# Sheet1.net
KiCad netlist of a schematic drawn in Altium Designer
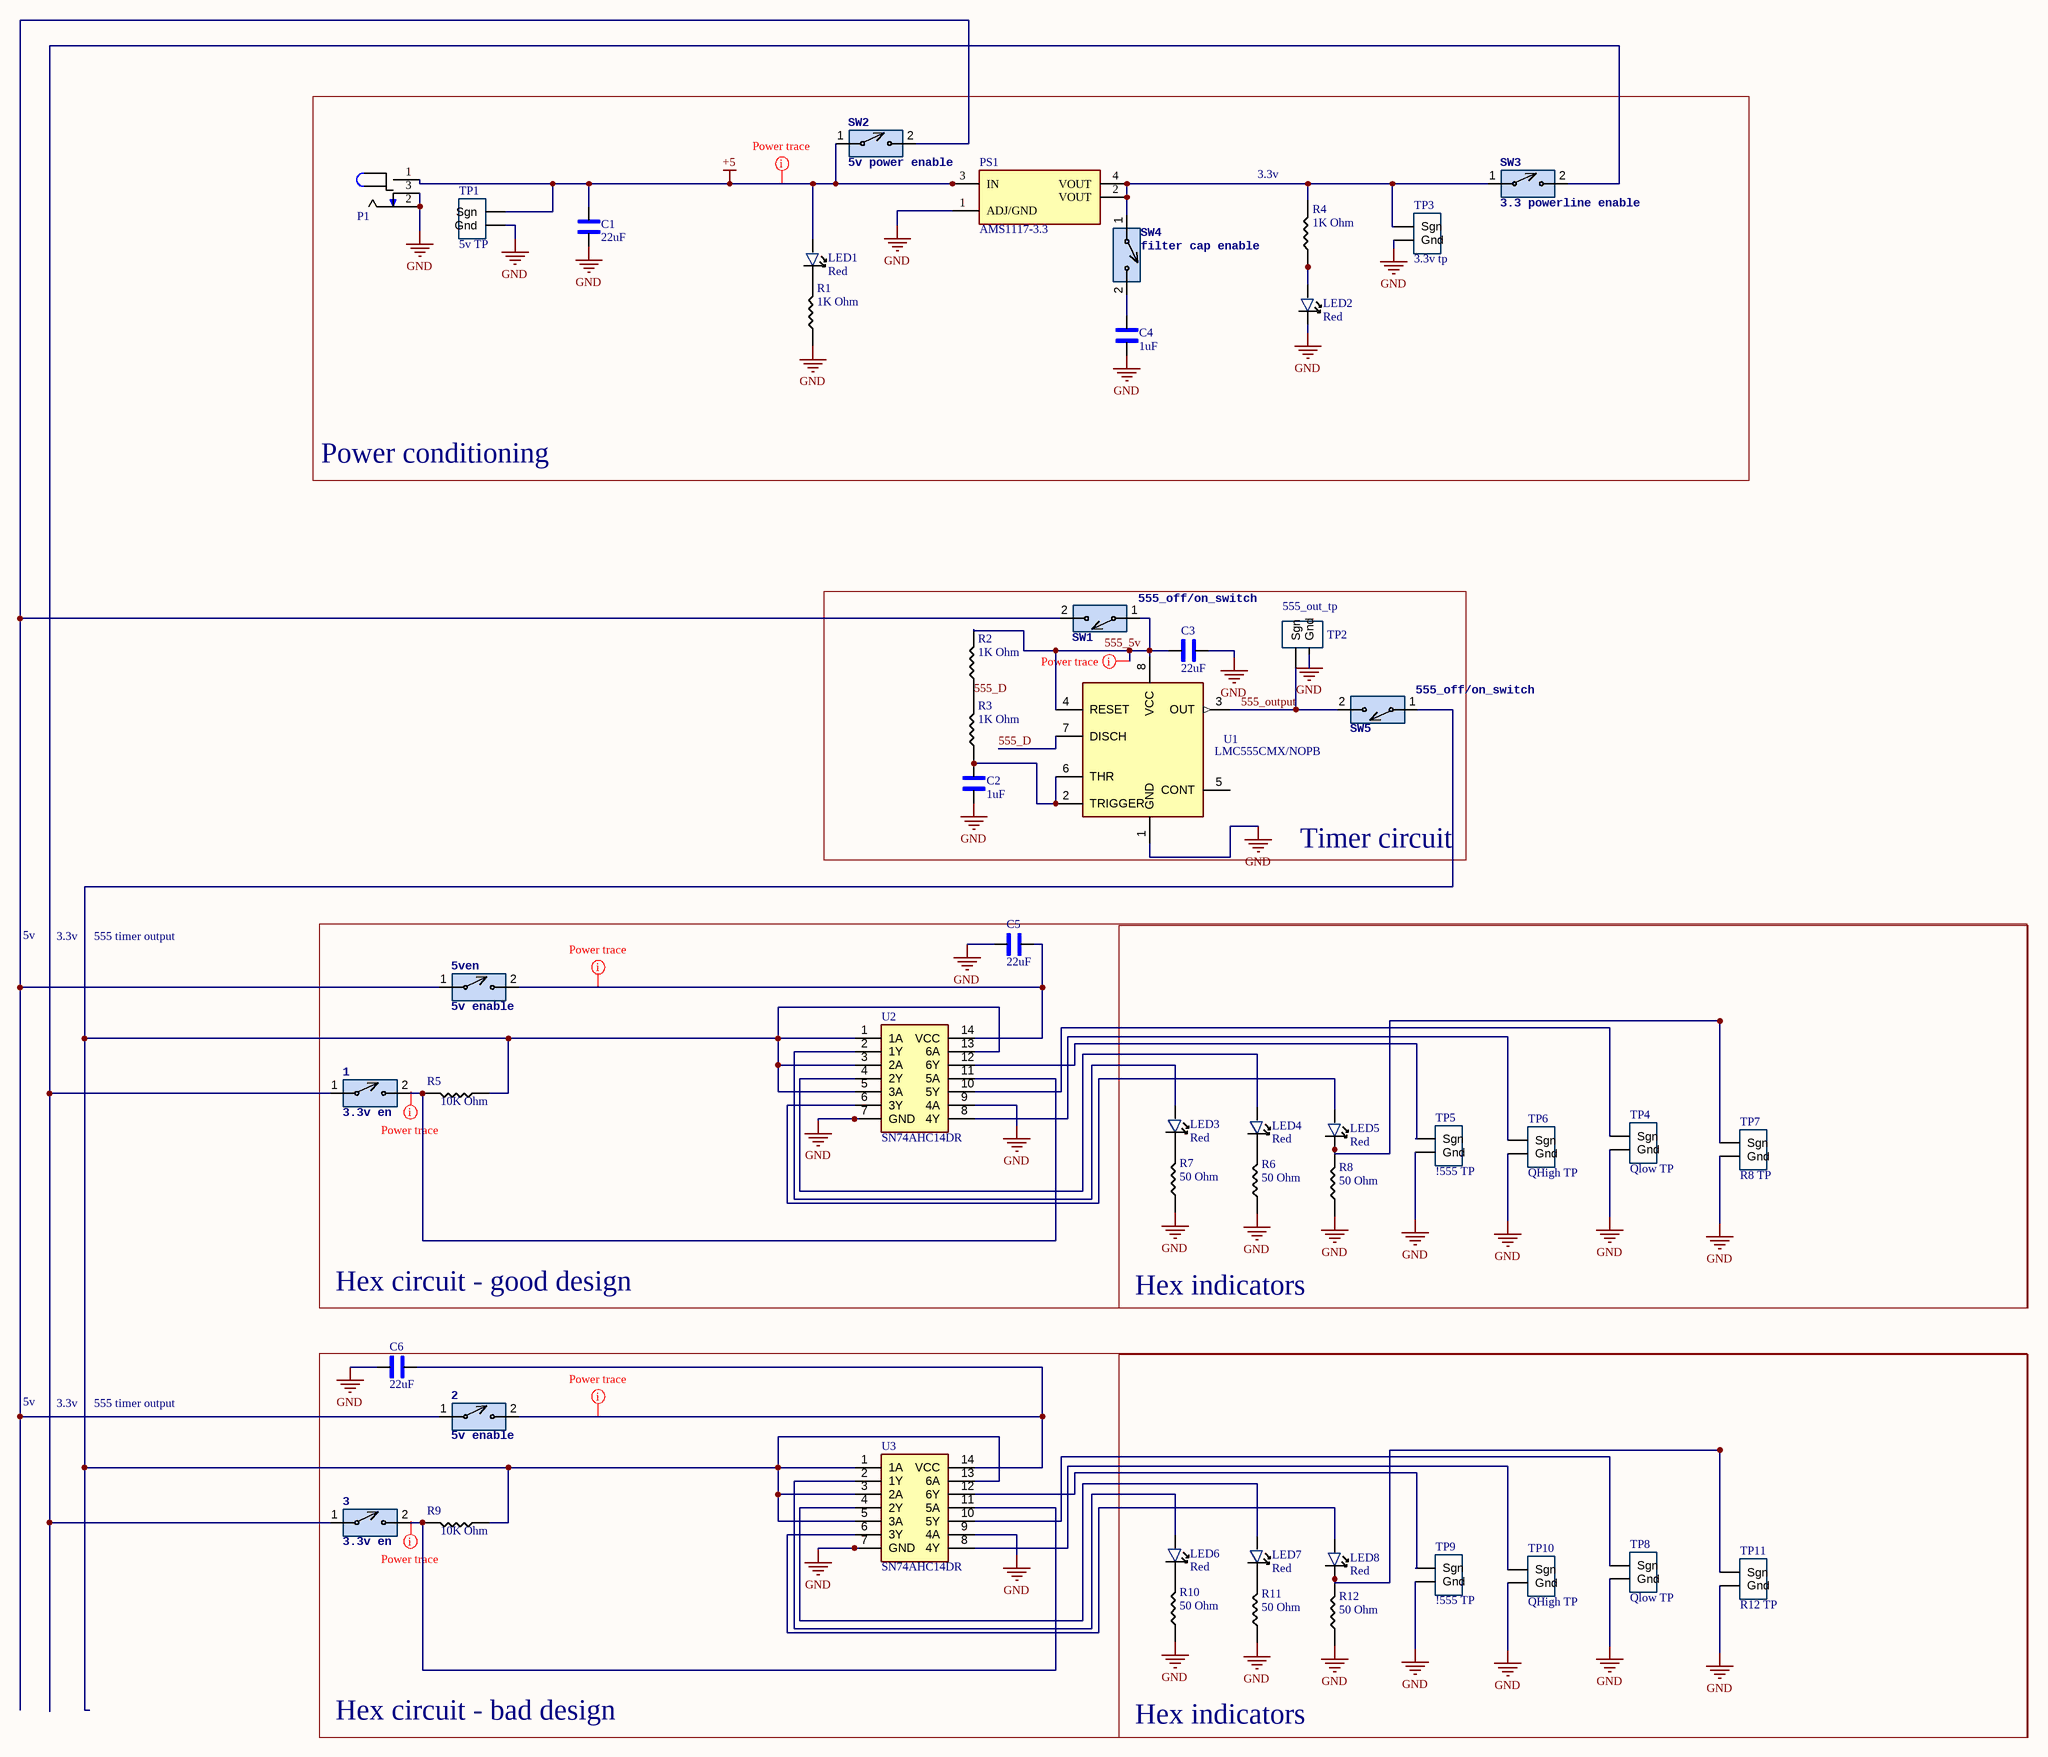
[diagram p0: Sheet1.SchDoc]

(export (version "E")
  (design (tool "Eeschema 10.0.6"))
  (components
    (comp (ref "1")
      (value "3.3v en")
      (footprint "2Pin-Header-Conn")
      (description "2Pin Header")
      (fields (field (name "LCSC PART#") "C124375"))
      (libsource (lib "ECEN5730Lib_2023_05_DS") (part "SW_2Pin_100mil_Switch"))
    )
    (comp (ref "2")
      (value "5v enable")
      (footprint "2Pin-Header-Conn")
      (description "2Pin Header")
      (fields (field (name "LCSC PART#") "C124375"))
      (libsource (lib "ECEN5730Lib_2023_05_DS") (part "SW_2Pin_100mil_Switch"))
    )
    (comp (ref "3")
      (value "3.3v en")
      (footprint "2Pin-Header-Conn")
      (description "2Pin Header")
      (fields (field (name "LCSC PART#") "C124375"))
      (libsource (lib "ECEN5730Lib_2023_05_DS") (part "SW_2Pin_100mil_Switch"))
    )
    (comp (ref "5ven")
      (value "5v enable")
      (footprint "2Pin-Header-Conn")
      (description "2Pin Header")
      (fields (field (name "LCSC PART#") "C124375"))
      (libsource (lib "ECEN5730Lib_2023_05_DS") (part "SW_2Pin_100mil_Switch"))
    )
    (comp (ref "C1")
      (value "22uF")
      (footprint "1206_Passive_Capacitor")
      (description "22uF ±10% 25V X5R 1206 Multilayer Ceramic Capacitors MLCC - SMD/SMT RoHS")
      (fields (field (name "MFR PART #") "CL31A226KAHNNNE") (field (name "LCSC PART#") "C12891"))
      (libsource (lib "ECEN5730Lib_2023_05_DS") (part "C_22uF_1206"))
    )
    (comp (ref "C2")
      (value "1uF")
      (footprint "1206_Passive_Capacitor")
      (description "MULTILAYER CERAMIC CAPACITORS MLCC - SMD/SMT 1UF 50V 1206 ROHS")
      (fields (field (name "MFR PART #") "CL31B105KBHNNNE") (field (name "LCSC PART#") "C1848"))
      (libsource (lib "ECEN5730Lib_2023_05_DS") (part "C_1uF_1206"))
    )
    (comp (ref "C3")
      (value "22uF")
      (footprint "1206_Passive_Capacitor")
      (description "22uF ±10% 25V X5R 1206 Multilayer Ceramic Capacitors MLCC - SMD/SMT RoHS")
      (fields (field (name "MFR PART #") "CL31A226KAHNNNE") (field (name "LCSC PART#") "C12891"))
      (libsource (lib "ECEN5730Lib_2023_05_DS") (part "C_22uF_1206"))
    )
    (comp (ref "C4")
      (value "1uF")
      (footprint "1206_Passive_Capacitor")
      (description "MULTILAYER CERAMIC CAPACITORS MLCC - SMD/SMT 1UF 50V 1206 ROHS")
      (fields (field (name "MFR PART #") "CL31B105KBHNNNE") (field (name "LCSC PART#") "C1848"))
      (libsource (lib "ECEN5730Lib_2023_05_DS") (part "C_1uF_1206"))
    )
    (comp (ref "C5")
      (value "22uF")
      (footprint "1206_Passive_Capacitor")
      (description "22uF ±10% 25V X5R 1206 Multilayer Ceramic Capacitors MLCC - SMD/SMT RoHS")
      (fields (field (name "MFR PART #") "CL31A226KAHNNNE") (field (name "LCSC PART#") "C12891"))
      (libsource (lib "ECEN5730Lib_2023_05_DS") (part "C_22uF_1206"))
    )
    (comp (ref "C6")
      (value "22uF")
      (footprint "1206_Passive_Capacitor")
      (description "22uF ±10% 25V X5R 1206 Multilayer Ceramic Capacitors MLCC - SMD/SMT RoHS")
      (fields (field (name "MFR PART #") "CL31A226KAHNNNE") (field (name "LCSC PART#") "C12891"))
      (libsource (lib "ECEN5730Lib_2023_05_DS") (part "C_22uF_1206"))
    )
    (comp (ref "LED1")
      (value "Red")
      (footprint "LED_1206")
      (description "Red 621~631nm 1206 Light Emitting Diodes (LED) RoHS")
      (fields (field (name "MFR PART #") "15-21/R6C-FQ1R1B/2T") (field (name "LCSC PART#") "C93133"))
      (libsource (lib "ECEN5730Lib_2023_05_DS") (part "LED_RED_1206"))
    )
    (comp (ref "LED2")
      (value "Red")
      (footprint "LED_1206")
      (description "Red 621~631nm 1206 Light Emitting Diodes (LED) RoHS")
      (fields (field (name "MFR PART #") "15-21/R6C-FQ1R1B/2T") (field (name "LCSC PART#") "C93133"))
      (libsource (lib "ECEN5730Lib_2023_05_DS") (part "LED_RED_1206"))
    )
    (comp (ref "LED3")
      (value "Red")
      (footprint "LED_1206")
      (description "Red 621~631nm 1206 Light Emitting Diodes (LED) RoHS")
      (fields (field (name "MFR PART #") "15-21/R6C-FQ1R1B/2T") (field (name "LCSC PART#") "C93133"))
      (libsource (lib "ECEN5730Lib_2023_05_DS") (part "LED_RED_1206"))
    )
    (comp (ref "LED4")
      (value "Red")
      (footprint "LED_1206")
      (description "Red 621~631nm 1206 Light Emitting Diodes (LED) RoHS")
      (fields (field (name "MFR PART #") "15-21/R6C-FQ1R1B/2T") (field (name "LCSC PART#") "C93133"))
      (libsource (lib "ECEN5730Lib_2023_05_DS") (part "LED_RED_1206"))
    )
    (comp (ref "LED5")
      (value "Red")
      (footprint "LED_1206")
      (description "Red 621~631nm 1206 Light Emitting Diodes (LED) RoHS")
      (fields (field (name "MFR PART #") "15-21/R6C-FQ1R1B/2T") (field (name "LCSC PART#") "C93133"))
      (libsource (lib "ECEN5730Lib_2023_05_DS") (part "LED_RED_1206"))
    )
    (comp (ref "LED6")
      (value "Red")
      (footprint "LED_1206")
      (description "Red 621~631nm 1206 Light Emitting Diodes (LED) RoHS")
      (fields (field (name "MFR PART #") "15-21/R6C-FQ1R1B/2T") (field (name "LCSC PART#") "C93133"))
      (libsource (lib "ECEN5730Lib_2023_05_DS") (part "LED_RED_1206"))
    )
    (comp (ref "LED7")
      (value "Red")
      (footprint "LED_1206")
      (description "Red 621~631nm 1206 Light Emitting Diodes (LED) RoHS")
      (fields (field (name "MFR PART #") "15-21/R6C-FQ1R1B/2T") (field (name "LCSC PART#") "C93133"))
      (libsource (lib "ECEN5730Lib_2023_05_DS") (part "LED_RED_1206"))
    )
    (comp (ref "LED8")
      (value "Red")
      (footprint "LED_1206")
      (description "Red 621~631nm 1206 Light Emitting Diodes (LED) RoHS")
      (fields (field (name "MFR PART #") "15-21/R6C-FQ1R1B/2T") (field (name "LCSC PART#") "C93133"))
      (libsource (lib "ECEN5730Lib_2023_05_DS") (part "LED_RED_1206"))
    )
    (comp (ref "P1")
      (value "Power Jack")
      (footprint "Power_Jack")
      (description "Power Barrel Connector Jack 2.10mm ID (0.083\"), 5.50mm OD (0.217\") Through Hole, Right Angle")
      (fields (field (name "MFR PART #") "PJ-102A") (field (name "LCSC PART#") "C136744"))
      (libsource (lib "ECEN5730Lib_2023_05_DS") (part "P_Power Jack"))
    )
    (comp (ref "PS1")
      (value "AMS1117-3.3")
      (footprint "LDO")
      (description "LOW DROPOUT REGULATORS(LDO) POSITIVE FIXED 1.3V @ 800MA 15V 3.3V 1A SOT-223 ROHS")
      (fields (field (name "LCSC PART#") "C6186"))
      (libsource (lib "ECEN5730Lib_2023_05_DS") (part "PS_AMS_LDO_3v3"))
    )
    (comp (ref "R1")
      (value "1K Ohm")
      (footprint "1206_Passive_Resitor")
      (description "CHIP RESISTOR - SURFACE MOUNT 1KOHMS ±1% 1/4W 1206 ROHS")
      (fields (field (name "MFR PART #") "RNCP1206FTD1K00CT") (field (name "LCSC PART#") "C4410"))
      (libsource (lib "ECEN5730Lib_2023_05_DS") (part "R_1K_1206"))
    )
    (comp (ref "R2")
      (value "1K Ohm")
      (footprint "1206_Passive_Resitor")
      (description "CHIP RESISTOR - SURFACE MOUNT 1KOHMS ±1% 1/4W 1206 ROHS")
      (fields (field (name "MFR PART #") "RNCP1206FTD1K00CT") (field (name "LCSC PART#") "C4410"))
      (libsource (lib "ECEN5730Lib_2023_05_DS") (part "R_1K_1206"))
    )
    (comp (ref "R3")
      (value "1K Ohm")
      (footprint "1206_Passive_Resitor")
      (description "CHIP RESISTOR - SURFACE MOUNT 1KOHMS ±1% 1/4W 1206 ROHS")
      (fields (field (name "MFR PART #") "RNCP1206FTD1K00CT") (field (name "LCSC PART#") "C4410"))
      (libsource (lib "ECEN5730Lib_2023_05_DS") (part "R_1K_1206"))
    )
    (comp (ref "R4")
      (value "1K Ohm")
      (footprint "1206_Passive_Resitor")
      (description "CHIP RESISTOR - SURFACE MOUNT 1KOHMS ±1% 1/4W 1206 ROHS")
      (fields (field (name "MFR PART #") "RNCP1206FTD1K00CT") (field (name "LCSC PART#") "C4410"))
      (libsource (lib "ECEN5730Lib_2023_05_DS") (part "R_1K_1206"))
    )
    (comp (ref "R5")
      (value "10K Ohm")
      (footprint "1206_Passive_Resitor")
      (description "CHIP RESISTOR - SURFACE MOUNT 1KOHMS ±1% 1/4W 1206 ROHS")
      (fields (field (name "MFR PART #") "RNCP1206FTD1K00CT") (field (name "LCSC PART#") "C4410"))
      (libsource (lib "ECEN5730Lib_2023_05_DS") (part "R_1K_1206"))
    )
    (comp (ref "R6")
      (value "50 Ohm")
      (footprint "1206_Passive_Resitor")
      (description "CHIP RESISTOR - SURFACE MOUNT 100MOHMS ±1% 1/4W 1206 ROHS")
      (fields (field (name "MFR PART #") "1206W4F1006T5E") (field (name "LCSC PART#") "C59781"))
      (libsource (lib "ECEN5730Lib_2023_05_DS") (part "R_100M_1206_1"))
    )
    (comp (ref "R7")
      (value "50 Ohm")
      (footprint "1206_Passive_Resitor")
      (description "CHIP RESISTOR - SURFACE MOUNT 100MOHMS ±1% 1/4W 1206 ROHS")
      (fields (field (name "MFR PART #") "1206W4F1006T5E") (field (name "LCSC PART#") "C59781"))
      (libsource (lib "ECEN5730Lib_2023_05_DS") (part "R_100M_1206_1"))
    )
    (comp (ref "R8")
      (value "50 Ohm")
      (footprint "1206_Passive_Resitor")
      (description "CHIP RESISTOR - SURFACE MOUNT 100MOHMS ±1% 1/4W 1206 ROHS")
      (fields (field (name "MFR PART #") "1206W4F1006T5E") (field (name "LCSC PART#") "C59781"))
      (libsource (lib "ECEN5730Lib_2023_05_DS") (part "R_100M_1206_1"))
    )
    (comp (ref "R9")
      (value "10K Ohm")
      (footprint "1206_Passive_Resitor")
      (description "CHIP RESISTOR - SURFACE MOUNT 1KOHMS ±1% 1/4W 1206 ROHS")
      (fields (field (name "MFR PART #") "RNCP1206FTD1K00CT") (field (name "LCSC PART#") "C4410"))
      (libsource (lib "ECEN5730Lib_2023_05_DS") (part "R_1K_1206"))
    )
    (comp (ref "R10")
      (value "50 Ohm")
      (footprint "1206_Passive_Resitor")
      (description "CHIP RESISTOR - SURFACE MOUNT 100MOHMS ±1% 1/4W 1206 ROHS")
      (fields (field (name "MFR PART #") "1206W4F1006T5E") (field (name "LCSC PART#") "C59781"))
      (libsource (lib "ECEN5730Lib_2023_05_DS") (part "R_100M_1206_1"))
    )
    (comp (ref "R11")
      (value "50 Ohm")
      (footprint "1206_Passive_Resitor")
      (description "CHIP RESISTOR - SURFACE MOUNT 100MOHMS ±1% 1/4W 1206 ROHS")
      (fields (field (name "MFR PART #") "1206W4F1006T5E") (field (name "LCSC PART#") "C59781"))
      (libsource (lib "ECEN5730Lib_2023_05_DS") (part "R_100M_1206_1"))
    )
    (comp (ref "R12")
      (value "50 Ohm")
      (footprint "1206_Passive_Resitor")
      (description "CHIP RESISTOR - SURFACE MOUNT 100MOHMS ±1% 1/4W 1206 ROHS")
      (fields (field (name "MFR PART #") "1206W4F1006T5E") (field (name "LCSC PART#") "C59781"))
      (libsource (lib "ECEN5730Lib_2023_05_DS") (part "R_100M_1206_1"))
    )
    (comp (ref "SW1")
      (value "555_off/on_switch")
      (footprint "2Pin-Header-Conn")
      (description "2Pin Header")
      (fields (field (name "LCSC PART#") "C124375"))
      (libsource (lib "") (part "SW_2Pin_100mil_Switch_1"))
    )
    (comp (ref "SW2")
      (value "5v power enable")
      (footprint "2Pin-Header-Conn")
      (description "2Pin Header")
      (fields (field (name "LCSC PART#") "C124375"))
      (libsource (lib "ECEN5730Lib_2023_05_DS") (part "SW_2Pin_100mil_Switch"))
    )
    (comp (ref "SW3")
      (value "3.3 powerline enable")
      (footprint "2Pin-Header-Conn")
      (description "2Pin Header")
      (fields (field (name "LCSC PART#") "C124375"))
      (libsource (lib "ECEN5730Lib_2023_05_DS") (part "SW_2Pin_100mil_Switch"))
    )
    (comp (ref "SW4")
      (value "filter cap enable")
      (footprint "2Pin-Header-Conn")
      (description "2Pin Header")
      (fields (field (name "LCSC PART#") "C124375"))
      (libsource (lib "") (part "SW_2Pin_100mil_Switch_2"))
    )
    (comp (ref "SW5")
      (value "555_off/on_switch")
      (footprint "2Pin-Header-Conn")
      (description "2Pin Header")
      (fields (field (name "LCSC PART#") "C124375"))
      (libsource (lib "") (part "SW_2Pin_100mil_Switch_1"))
    )
    (comp (ref "TP1")
      (value "5v TP")
      (footprint "TP10x_Probe")
      (description "Test Point 300 mil centers")
      (libsource (lib "") (part "TP_10x_Probe_1"))
    )
    (comp (ref "TP2")
      (value "555_out_tp")
      (footprint "TP10x_Probe")
      (description "Test Point 300 mil centers")
      (libsource (lib "") (part "TP_10x_Probe_2"))
    )
    (comp (ref "TP3")
      (value "3.3v tp")
      (footprint "TP10x_Probe")
      (description "Test Point 300 mil centers")
      (libsource (lib "ECEN5730Lib_2023_05_DS") (part "TP_10x_Probe"))
    )
    (comp (ref "TP4")
      (value "Qlow TP")
      (footprint "TP10x_Probe")
      (description "Test Point 300 mil centers")
      (libsource (lib "ECEN5730Lib_2023_05_DS") (part "TP_10x_Probe"))
    )
    (comp (ref "TP5")
      (value "!555 TP")
      (footprint "TP10x_Probe")
      (description "Test Point 300 mil centers")
      (libsource (lib "ECEN5730Lib_2023_05_DS") (part "TP_10x_Probe"))
    )
    (comp (ref "TP6")
      (value "QHigh TP")
      (footprint "TP10x_Probe")
      (description "Test Point 300 mil centers")
      (libsource (lib "ECEN5730Lib_2023_05_DS") (part "TP_10x_Probe"))
    )
    (comp (ref "TP7")
      (value "R8 TP")
      (footprint "TP10x_Probe")
      (description "Test Point 300 mil centers")
      (libsource (lib "ECEN5730Lib_2023_05_DS") (part "TP_10x_Probe"))
    )
    (comp (ref "TP8")
      (value "Qlow TP")
      (footprint "TP10x_Probe")
      (description "Test Point 300 mil centers")
      (libsource (lib "ECEN5730Lib_2023_05_DS") (part "TP_10x_Probe"))
    )
    (comp (ref "TP9")
      (value "!555 TP")
      (footprint "TP10x_Probe")
      (description "Test Point 300 mil centers")
      (libsource (lib "ECEN5730Lib_2023_05_DS") (part "TP_10x_Probe"))
    )
    (comp (ref "TP10")
      (value "QHigh TP")
      (footprint "TP10x_Probe")
      (description "Test Point 300 mil centers")
      (libsource (lib "ECEN5730Lib_2023_05_DS") (part "TP_10x_Probe"))
    )
    (comp (ref "TP11")
      (value "R12 TP")
      (footprint "TP10x_Probe")
      (description "Test Point 300 mil centers")
      (libsource (lib "ECEN5730Lib_2023_05_DS") (part "TP_10x_Probe"))
    )
    (comp (ref "U1")
      (value "LMC555CMX/NOPB")
      (footprint "TS555IDTTR")
      (description "555 Type, Timer/Oscillator _Single_ IC 3MHz 8-SO")
      (fields (field (name "LCSC PART#") "C90760"))
      (libsource (lib "ECEN5730Lib_2023_05_DS") (part "U_555_Fast"))
    )
    (comp (ref "U2")
      (value "SN74AHC14DR")
      (footprint "HEX_74AC14")
      (description "Inverter IC 6 Channel Schmitt Trigger 14-SOIC")
      (fields (field (name "LCSC PART#") "C6942"))
      (libsource (lib "ECEN5730Lib_2023_05_DS") (part "U_74AHC14"))
    )
    (comp (ref "U3")
      (value "SN74AHC14DR")
      (footprint "HEX_74AC14")
      (description "Inverter IC 6 Channel Schmitt Trigger 14-SOIC")
      (fields (field (name "LCSC PART#") "C6942"))
      (libsource (lib "ECEN5730Lib_2023_05_DS") (part "U_74AHC14"))
    )
  )
  (nets
    (net (code "1") (name "+5") (class "Default")
      (node (ref "C1") (pin "2") (pinfunction "2_2") (pintype "passive"))
      (node (ref "LED1") (pin "1") (pinfunction "1_1") (pintype "passive"))
      (node (ref "P1") (pin "1") (pinfunction "1_1") (pintype "power_in"))
      (node (ref "PS1") (pin "3") (pinfunction "IN_3") (pintype "power_in"))
      (node (ref "SW2") (pin "1") (pinfunction "1_1") (pintype "passive"))
      (node (ref "TP1") (pin "1") (pinfunction "Sgn_1") (pintype "passive"))
    )
    (net (code "2") (name "/555_5v") (class "Default")
      (node (ref "C3") (pin "1") (pinfunction "1_1") (pintype "passive"))
      (node (ref "R2") (pin "2") (pinfunction "2_2") (pintype "passive"))
      (node (ref "SW1") (pin "1") (pinfunction "1_1") (pintype "passive"))
      (node (ref "U1") (pin "4") (pinfunction "RESET_4") (pintype "passive"))
      (node (ref "U1") (pin "8") (pinfunction "VCC_8") (pintype "power_in"))
    )
    (net (code "3") (name "/555_D") (class "Default")
      (node (ref "R2") (pin "1") (pinfunction "1_1") (pintype "passive"))
      (node (ref "R3") (pin "2") (pinfunction "2_2") (pintype "passive"))
      (node (ref "U1") (pin "7") (pinfunction "DISCH_7") (pintype "passive"))
    )
    (net (code "4") (name "/555_output") (class "Default")
      (node (ref "SW5") (pin "2") (pinfunction "2_2") (pintype "passive"))
      (node (ref "TP2") (pin "1") (pinfunction "Sgn_1") (pintype "passive"))
      (node (ref "U1") (pin "3") (pinfunction "OUT_3") (pintype "output"))
    )
    (net (code "5") (name "GND") (class "Default")
      (node (ref "C1") (pin "1") (pinfunction "1_1") (pintype "passive"))
      (node (ref "C2") (pin "1") (pinfunction "1_1") (pintype "passive"))
      (node (ref "C3") (pin "2") (pinfunction "2_2") (pintype "passive"))
      (node (ref "C4") (pin "1") (pinfunction "1_1") (pintype "passive"))
      (node (ref "C5") (pin "1") (pinfunction "1_1") (pintype "passive"))
      (node (ref "C6") (pin "1") (pinfunction "1_1") (pintype "passive"))
      (node (ref "LED2") (pin "2") (pinfunction "2_2") (pintype "passive"))
      (node (ref "P1") (pin "2") (pinfunction "2_2") (pintype "power_in"))
      (node (ref "P1") (pin "3") (pinfunction "3_3") (pintype "power_in"))
      (node (ref "PS1") (pin "1") (pinfunction "ADJ/GND_1") (pintype "passive"))
      (node (ref "R1") (pin "1") (pinfunction "1_1") (pintype "passive"))
      (node (ref "R10") (pin "1") (pinfunction "1_1") (pintype "passive"))
      (node (ref "R11") (pin "1") (pinfunction "1_1") (pintype "passive"))
      (node (ref "R12") (pin "1") (pinfunction "1_1") (pintype "passive"))
      (node (ref "R6") (pin "1") (pinfunction "1_1") (pintype "passive"))
      (node (ref "R7") (pin "1") (pinfunction "1_1") (pintype "passive"))
      (node (ref "R8") (pin "1") (pinfunction "1_1") (pintype "passive"))
      (node (ref "TP1") (pin "2") (pinfunction "Gnd_2") (pintype "passive"))
      (node (ref "TP10") (pin "2") (pinfunction "Gnd_2") (pintype "passive"))
      (node (ref "TP11") (pin "2") (pinfunction "Gnd_2") (pintype "passive"))
      (node (ref "TP2") (pin "2") (pinfunction "Gnd_2") (pintype "passive"))
      (node (ref "TP3") (pin "2") (pinfunction "Gnd_2") (pintype "passive"))
      (node (ref "TP4") (pin "2") (pinfunction "Gnd_2") (pintype "passive"))
      (node (ref "TP5") (pin "2") (pinfunction "Gnd_2") (pintype "passive"))
      (node (ref "TP6") (pin "2") (pinfunction "Gnd_2") (pintype "passive"))
      (node (ref "TP7") (pin "2") (pinfunction "Gnd_2") (pintype "passive"))
      (node (ref "TP8") (pin "2") (pinfunction "Gnd_2") (pintype "passive"))
      (node (ref "TP9") (pin "2") (pinfunction "Gnd_2") (pintype "passive"))
      (node (ref "U1") (pin "1") (pinfunction "GND_1") (pintype "power_in"))
      (node (ref "U2") (pin "7") (pinfunction "GND_7") (pintype "passive"))
      (node (ref "U2") (pin "9") (pinfunction "4A_9") (pintype "passive"))
      (node (ref "U3") (pin "7") (pinfunction "GND_7") (pintype "passive"))
      (node (ref "U3") (pin "9") (pinfunction "4A_9") (pintype "passive"))
    )
    (net (code "6") (name "Net-(1-Pad1)") (class "Default")
      (node (ref "1") (pin "1") (pinfunction "1_1") (pintype "passive"))
      (node (ref "3") (pin "1") (pinfunction "1_1") (pintype "passive"))
      (node (ref "SW3") (pin "2") (pinfunction "2_2") (pintype "passive"))
    )
    (net (code "7") (name "Net-(2-Pad1)") (class "Default")
      (node (ref "2") (pin "1") (pinfunction "1_1") (pintype "passive"))
      (node (ref "5ven") (pin "1") (pinfunction "1_1") (pintype "passive"))
      (node (ref "SW1") (pin "2") (pinfunction "2_2") (pintype "passive"))
      (node (ref "SW2") (pin "2") (pinfunction "2_2") (pintype "passive"))
    )
    (net (code "8") (name "Net-(C4-Pad2)") (class "Default")
      (node (ref "C4") (pin "2") (pinfunction "2_2") (pintype "passive"))
      (node (ref "SW4") (pin "2") (pinfunction "2_2") (pintype "passive"))
    )
    (net (code "9") (name "Net-(LED1-Pad2)") (class "Default")
      (node (ref "LED1") (pin "2") (pinfunction "2_2") (pintype "passive"))
      (node (ref "R1") (pin "2") (pinfunction "2_2") (pintype "passive"))
    )
    (net (code "10") (name "Net-(LED2-Pad1)") (class "Default")
      (node (ref "LED2") (pin "1") (pinfunction "1_1") (pintype "passive"))
      (node (ref "R4") (pin "1") (pinfunction "1_1") (pintype "passive"))
    )
    (net (code "11") (name "Net-(LED3-Pad2)") (class "Default")
      (node (ref "LED3") (pin "2") (pinfunction "2_2") (pintype "passive"))
      (node (ref "R7") (pin "2") (pinfunction "2_2") (pintype "passive"))
    )
    (net (code "12") (name "Net-(LED4-Pad2)") (class "Default")
      (node (ref "LED4") (pin "2") (pinfunction "2_2") (pintype "passive"))
      (node (ref "R6") (pin "2") (pinfunction "2_2") (pintype "passive"))
    )
    (net (code "13") (name "Net-(LED6-Pad2)") (class "Default")
      (node (ref "LED6") (pin "2") (pinfunction "2_2") (pintype "passive"))
      (node (ref "R10") (pin "2") (pinfunction "2_2") (pintype "passive"))
    )
    (net (code "14") (name "Net-(LED7-Pad2)") (class "Default")
      (node (ref "LED7") (pin "2") (pinfunction "2_2") (pintype "passive"))
      (node (ref "R11") (pin "2") (pinfunction "2_2") (pintype "passive"))
    )
    (net (code "15") (name "Net-(TP3-Sgn)") (class "Default")
      (node (ref "PS1") (pin "2") (pinfunction "VOUT_2") (pintype "power_in"))
      (node (ref "PS1") (pin "4") (pinfunction "VOUT_4") (pintype "power_in"))
      (node (ref "R4") (pin "2") (pinfunction "2_2") (pintype "passive"))
      (node (ref "SW3") (pin "1") (pinfunction "1_1") (pintype "passive"))
      (node (ref "SW4") (pin "1") (pinfunction "1_1") (pintype "passive"))
      (node (ref "TP3") (pin "1") (pinfunction "Sgn_1") (pintype "passive"))
    )
    (net (code "16") (name "Net-(TP4-Sgn)") (class "Default")
      (node (ref "TP4") (pin "1") (pinfunction "Sgn_1") (pintype "passive"))
      (node (ref "U2") (pin "10") (pinfunction "5Y_10") (pintype "passive"))
    )
    (net (code "17") (name "Net-(TP5-Sgn)") (class "Default")
      (node (ref "TP5") (pin "1") (pinfunction "Sgn_1") (pintype "passive"))
      (node (ref "U2") (pin "12") (pinfunction "6Y_12") (pintype "passive"))
    )
    (net (code "18") (name "Net-(TP6-Sgn)") (class "Default")
      (node (ref "TP6") (pin "1") (pinfunction "Sgn_1") (pintype "passive"))
      (node (ref "U2") (pin "8") (pinfunction "4Y_8") (pintype "passive"))
    )
    (net (code "19") (name "Net-(TP7-Sgn)") (class "Default")
      (node (ref "LED5") (pin "2") (pinfunction "2_2") (pintype "passive"))
      (node (ref "R8") (pin "2") (pinfunction "2_2") (pintype "passive"))
      (node (ref "TP7") (pin "1") (pinfunction "Sgn_1") (pintype "passive"))
    )
    (net (code "20") (name "Net-(TP8-Sgn)") (class "Default")
      (node (ref "TP8") (pin "1") (pinfunction "Sgn_1") (pintype "passive"))
      (node (ref "U3") (pin "10") (pinfunction "5Y_10") (pintype "passive"))
    )
    (net (code "21") (name "Net-(TP9-Sgn)") (class "Default")
      (node (ref "TP9") (pin "1") (pinfunction "Sgn_1") (pintype "passive"))
      (node (ref "U3") (pin "12") (pinfunction "6Y_12") (pintype "passive"))
    )
    (net (code "22") (name "Net-(TP10-Sgn)") (class "Default")
      (node (ref "TP10") (pin "1") (pinfunction "Sgn_1") (pintype "passive"))
      (node (ref "U3") (pin "8") (pinfunction "4Y_8") (pintype "passive"))
    )
    (net (code "23") (name "Net-(TP11-Sgn)") (class "Default")
      (node (ref "LED8") (pin "2") (pinfunction "2_2") (pintype "passive"))
      (node (ref "R12") (pin "2") (pinfunction "2_2") (pintype "passive"))
      (node (ref "TP11") (pin "1") (pinfunction "Sgn_1") (pintype "passive"))
    )
    (net (code "24") (name "Net-(U1-THR)") (class "Default")
      (node (ref "C2") (pin "2") (pinfunction "2_2") (pintype "passive"))
      (node (ref "R3") (pin "1") (pinfunction "1_1") (pintype "passive"))
      (node (ref "U1") (pin "2") (pinfunction "TRIGGER_2") (pintype "passive"))
      (node (ref "U1") (pin "6") (pinfunction "THR_6") (pintype "passive"))
    )
    (net (code "25") (name "Net-(U2-1A)") (class "Default")
      (node (ref "R5") (pin "1") (pinfunction "1_1") (pintype "passive"))
      (node (ref "R9") (pin "1") (pinfunction "1_1") (pintype "passive"))
      (node (ref "SW5") (pin "1") (pinfunction "1_1") (pintype "passive"))
      (node (ref "U2") (pin "1") (pinfunction "1A_1") (pintype "passive"))
      (node (ref "U2") (pin "13") (pinfunction "6A_13") (pintype "passive"))
      (node (ref "U2") (pin "3") (pinfunction "2A_3") (pintype "passive"))
      (node (ref "U2") (pin "5") (pinfunction "3A_5") (pintype "passive"))
      (node (ref "U3") (pin "1") (pinfunction "1A_1") (pintype "passive"))
      (node (ref "U3") (pin "13") (pinfunction "6A_13") (pintype "passive"))
      (node (ref "U3") (pin "3") (pinfunction "2A_3") (pintype "passive"))
      (node (ref "U3") (pin "5") (pinfunction "3A_5") (pintype "passive"))
    )
    (net (code "26") (name "Net-(U2-1Y)") (class "Default")
      (node (ref "LED3") (pin "1") (pinfunction "1_1") (pintype "passive"))
      (node (ref "U2") (pin "2") (pinfunction "1Y_2") (pintype "passive"))
    )
    (net (code "27") (name "Net-(U2-2Y)") (class "Default")
      (node (ref "LED4") (pin "1") (pinfunction "1_1") (pintype "passive"))
      (node (ref "U2") (pin "4") (pinfunction "2Y_4") (pintype "passive"))
    )
    (net (code "28") (name "Net-(U2-3Y)") (class "Default")
      (node (ref "LED5") (pin "1") (pinfunction "1_1") (pintype "passive"))
      (node (ref "U2") (pin "6") (pinfunction "3Y_6") (pintype "passive"))
    )
    (net (code "29") (name "Net-(U2-5A)") (class "Default")
      (node (ref "1") (pin "2") (pinfunction "2_2") (pintype "passive"))
      (node (ref "R5") (pin "2") (pinfunction "2_2") (pintype "passive"))
      (node (ref "U2") (pin "11") (pinfunction "5A_11") (pintype "passive"))
    )
    (net (code "30") (name "Net-(U2-VCC)") (class "Default")
      (node (ref "5ven") (pin "2") (pinfunction "2_2") (pintype "passive"))
      (node (ref "C5") (pin "2") (pinfunction "2_2") (pintype "passive"))
      (node (ref "U2") (pin "14") (pinfunction "VCC_14") (pintype "passive"))
    )
    (net (code "31") (name "Net-(U3-1Y)") (class "Default")
      (node (ref "LED6") (pin "1") (pinfunction "1_1") (pintype "passive"))
      (node (ref "U3") (pin "2") (pinfunction "1Y_2") (pintype "passive"))
    )
    (net (code "32") (name "Net-(U3-2Y)") (class "Default")
      (node (ref "LED7") (pin "1") (pinfunction "1_1") (pintype "passive"))
      (node (ref "U3") (pin "4") (pinfunction "2Y_4") (pintype "passive"))
    )
    (net (code "33") (name "Net-(U3-3Y)") (class "Default")
      (node (ref "LED8") (pin "1") (pinfunction "1_1") (pintype "passive"))
      (node (ref "U3") (pin "6") (pinfunction "3Y_6") (pintype "passive"))
    )
    (net (code "34") (name "Net-(U3-5A)") (class "Default")
      (node (ref "3") (pin "2") (pinfunction "2_2") (pintype "passive"))
      (node (ref "R9") (pin "2") (pinfunction "2_2") (pintype "passive"))
      (node (ref "U3") (pin "11") (pinfunction "5A_11") (pintype "passive"))
    )
    (net (code "35") (name "Net-(U3-VCC)") (class "Default")
      (node (ref "2") (pin "2") (pinfunction "2_2") (pintype "passive"))
      (node (ref "C6") (pin "2") (pinfunction "2_2") (pintype "passive"))
      (node (ref "U3") (pin "14") (pinfunction "VCC_14") (pintype "passive"))
    )
    (net (code "36") (name "unconnected-(U1-CONT-Pad5)") (class "Default")
      (node (ref "U1") (pin "5") (pinfunction "CONT_5") (pintype "passive"))
    )
  )
)
